# Hydrophone.net
KiCad netlist of a schematic drawn in Altium Designer
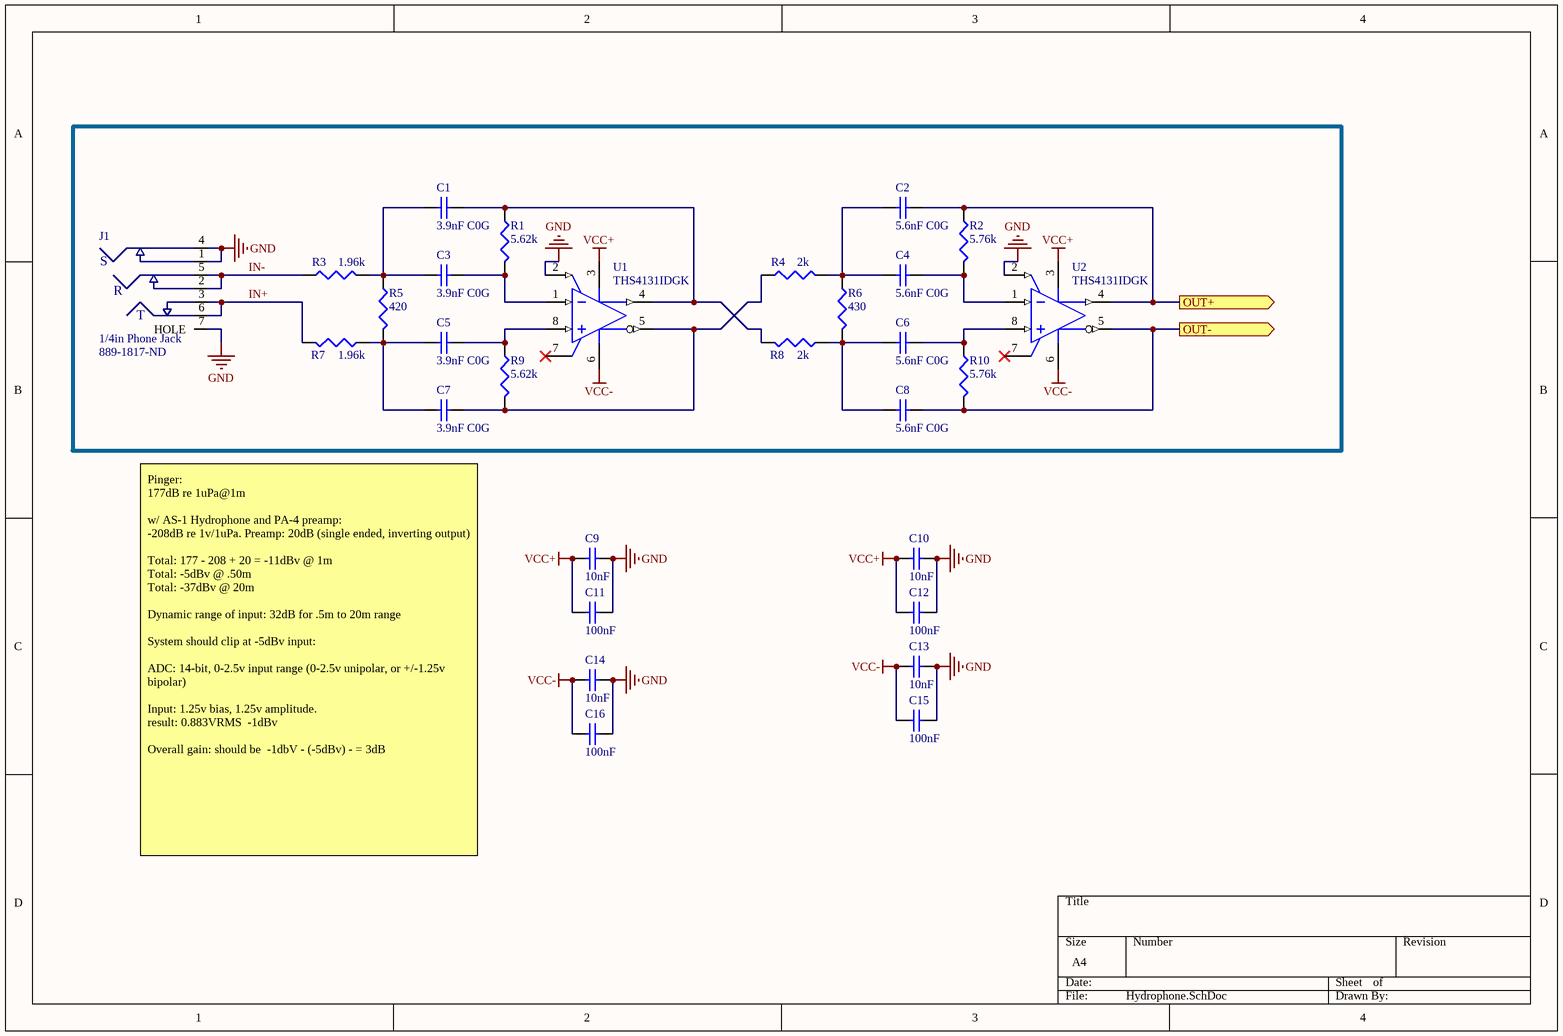
[diagram p0: Hydrophone.SchDoc]

(export (version "E")
  (design (tool "Eeschema 10.0.6"))
  (components
    (comp (ref "C1")
      (value "3.9nF C0G")
      (footprint "CAPC0603(1608)100_M")
      (description "CAP 3.9nF 50V ±20% 0603 (1608 Metric) Thickness 1mm SMD")
      (fields (field (name "TOLERANCE") "Â±20%"))
      (libsource (lib "Altium Content Vault") (part "CAP"))
    )
    (comp (ref "C2")
      (value "5.6nF C0G")
      (footprint "CAPC0603(1608)100_M")
      (description "CAP 5.6nF 50V ±10% 0603 (1608 Metric) Thickness 1mm SMD")
      (fields (field (name "TOLERANCE") "Â±10%"))
      (libsource (lib "Altium Content Vault") (part "CAP"))
    )
    (comp (ref "C3")
      (value "3.9nF C0G")
      (footprint "CAPC0603(1608)100_M")
      (description "CAP 3.9nF 50V ±20% 0603 (1608 Metric) Thickness 1mm SMD")
      (fields (field (name "TOLERANCE") "Â±20%"))
      (libsource (lib "Altium Content Vault") (part "CAP"))
    )
    (comp (ref "C4")
      (value "5.6nF C0G")
      (footprint "CAPC0603(1608)100_M")
      (description "CAP 5.6nF 50V ±10% 0603 (1608 Metric) Thickness 1mm SMD")
      (fields (field (name "TOLERANCE") "Â±10%"))
      (libsource (lib "Altium Content Vault") (part "CAP"))
    )
    (comp (ref "C5")
      (value "3.9nF C0G")
      (footprint "CAPC0603(1608)100_M")
      (description "CAP 3.9nF 50V ±20% 0603 (1608 Metric) Thickness 1mm SMD")
      (fields (field (name "TOLERANCE") "Â±20%"))
      (libsource (lib "Altium Content Vault") (part "CAP"))
    )
    (comp (ref "C6")
      (value "5.6nF C0G")
      (footprint "CAPC0603(1608)100_M")
      (description "CAP 5.6nF 50V ±10% 0603 (1608 Metric) Thickness 1mm SMD")
      (fields (field (name "TOLERANCE") "Â±10%"))
      (libsource (lib "Altium Content Vault") (part "CAP"))
    )
    (comp (ref "C7")
      (value "3.9nF C0G")
      (footprint "CAPC0603(1608)100_M")
      (description "CAP 3.9nF 50V ±20% 0603 (1608 Metric) Thickness 1mm SMD")
      (fields (field (name "TOLERANCE") "Â±20%"))
      (libsource (lib "Altium Content Vault") (part "CAP"))
    )
    (comp (ref "C8")
      (value "5.6nF C0G")
      (footprint "CAPC0603(1608)100_M")
      (description "CAP 5.6nF 50V ±10% 0603 (1608 Metric) Thickness 1mm SMD")
      (fields (field (name "TOLERANCE") "Â±10%"))
      (libsource (lib "Altium Content Vault") (part "CAP"))
    )
    (comp (ref "C9")
      (value "10nF")
      (footprint "CAPC0603(1608)100_M")
      (description "CAP 10nF 50V ±10% 0603 (1608 Metric) Thickness 1mm SMD")
      (fields (field (name "TOLERANCE") "Â±10%"))
      (libsource (lib "Altium Content Vault") (part "CAP"))
    )
    (comp (ref "C10")
      (value "10nF")
      (footprint "CAPC0603(1608)100_M")
      (description "CAP 10nF 50V ±10% 0603 (1608 Metric) Thickness 1mm SMD")
      (fields (field (name "TOLERANCE") "Â±10%"))
      (libsource (lib "Altium Content Vault") (part "CAP"))
    )
    (comp (ref "C11")
      (value "100nF")
      (footprint "CAPC0603(1608)100_M")
      (description "CAP 100nF 50V ±20% 0603 (1608 Metric) Thickness 1mm SMD")
      (fields (field (name "TOLERANCE") "Â±20%"))
      (libsource (lib "Altium Content Vault") (part "CAP"))
    )
    (comp (ref "C12")
      (value "100nF")
      (footprint "CAPC0603(1608)100_M")
      (description "CAP 100nF 50V ±20% 0603 (1608 Metric) Thickness 1mm SMD")
      (fields (field (name "TOLERANCE") "Â±20%"))
      (libsource (lib "Altium Content Vault") (part "CAP"))
    )
    (comp (ref "C13")
      (value "10nF")
      (footprint "CAPC0603(1608)100_M")
      (description "CAP 10nF 50V ±10% 0603 (1608 Metric) Thickness 1mm SMD")
      (fields (field (name "TOLERANCE") "Â±10%"))
      (libsource (lib "Altium Content Vault") (part "CAP"))
    )
    (comp (ref "C14")
      (value "10nF")
      (footprint "CAPC0603(1608)100_M")
      (description "CAP 10nF 50V ±10% 0603 (1608 Metric) Thickness 1mm SMD")
      (fields (field (name "TOLERANCE") "Â±10%"))
      (libsource (lib "Altium Content Vault") (part "CAP"))
    )
    (comp (ref "C15")
      (value "100nF")
      (footprint "CAPC0603(1608)100_M")
      (description "CAP 100nF 50V ±20% 0603 (1608 Metric) Thickness 1mm SMD")
      (fields (field (name "TOLERANCE") "Â±20%"))
      (libsource (lib "Altium Content Vault") (part "CAP"))
    )
    (comp (ref "C16")
      (value "100nF")
      (footprint "CAPC0603(1608)100_M")
      (description "CAP 100nF 50V ±20% 0603 (1608 Metric) Thickness 1mm SMD")
      (fields (field (name "TOLERANCE") "Â±20%"))
      (libsource (lib "Altium Content Vault") (part "CAP"))
    )
    (comp (ref "J1")
      (value "1/4in Phone Jack")
      (footprint "ACJS-MHDR")
      (fields (field (name "SUPPLIER PART NUMBER 1") "889-1817-ND"))
      (libsource (lib "Tauv-Lib") (part "ACJS-MHDR"))
    )
    (comp (ref "R1")
      (value "5.62k")
      (footprint "J1-0603")
      (description "Resistor")
      (fields (field (name "Comment") "Res3") (field (name "PUBLISHER") "Altium Limited"))
      (libsource (lib "Miscellaneous Devices") (part "Res3"))
    )
    (comp (ref "R2")
      (value "5.76k")
      (footprint "J1-0603")
      (description "Resistor")
      (fields (field (name "Comment") "Res3") (field (name "PUBLISHER") "Altium Limited"))
      (libsource (lib "Miscellaneous Devices") (part "Res3"))
    )
    (comp (ref "R3")
      (value "1.96k")
      (footprint "J1-0603")
      (description "Resistor")
      (fields (field (name "Comment") "Res3") (field (name "PUBLISHER") "Altium Limited"))
      (libsource (lib "Miscellaneous Devices") (part "Res3"))
    )
    (comp (ref "R4")
      (value "2k")
      (footprint "J1-0603")
      (description "Resistor")
      (fields (field (name "Comment") "Res3") (field (name "PUBLISHER") "Altium Limited"))
      (libsource (lib "Miscellaneous Devices") (part "Res3"))
    )
    (comp (ref "R5")
      (value "420")
      (footprint "J1-0603")
      (description "Resistor")
      (fields (field (name "Comment") "Res3") (field (name "PUBLISHER") "Altium Limited"))
      (libsource (lib "Miscellaneous Devices") (part "Res3"))
    )
    (comp (ref "R6")
      (value "430")
      (footprint "J1-0603")
      (description "Resistor")
      (fields (field (name "Comment") "Res3") (field (name "PUBLISHER") "Altium Limited"))
      (libsource (lib "Miscellaneous Devices") (part "Res3"))
    )
    (comp (ref "R7")
      (value "1.96k")
      (footprint "J1-0603")
      (description "Resistor")
      (fields (field (name "Comment") "Res3") (field (name "PUBLISHER") "Altium Limited"))
      (libsource (lib "Miscellaneous Devices") (part "Res3"))
    )
    (comp (ref "R8")
      (value "2k")
      (footprint "J1-0603")
      (description "Resistor")
      (fields (field (name "Comment") "Res3") (field (name "PUBLISHER") "Altium Limited"))
      (libsource (lib "Miscellaneous Devices") (part "Res3"))
    )
    (comp (ref "R9")
      (value "5.62k")
      (footprint "J1-0603")
      (description "Resistor")
      (fields (field (name "Comment") "Res3") (field (name "PUBLISHER") "Altium Limited"))
      (libsource (lib "Miscellaneous Devices") (part "Res3"))
    )
    (comp (ref "R10")
      (value "5.76k")
      (footprint "J1-0603")
      (description "Resistor")
      (fields (field (name "Comment") "Res3") (field (name "PUBLISHER") "Altium Limited"))
      (libsource (lib "Miscellaneous Devices") (part "Res3"))
    )
    (comp (ref "U1")
      (value "THS4131IDGK")
      (footprint "DGK0008A_N")
      (fields (field (name "MANUFACTURER") "Texas Instruments"))
      (libsource (lib "Altium Content Vault") (part "TI-THS41X1-8"))
    )
    (comp (ref "U2")
      (value "THS4131IDGK")
      (footprint "DGK0008A_N")
      (fields (field (name "MANUFACTURER") "Texas Instruments"))
      (libsource (lib "Altium Content Vault") (part "TI-THS41X1-8"))
    )
  )
  (nets
    (net (code "1") (name "/IN+") (class "Default")
      (node (ref "J1") (pin "3") (pinfunction "3_3") (pintype "passive"))
      (node (ref "J1") (pin "6") (pinfunction "6_6") (pintype "passive"))
      (node (ref "R7") (pin "2") (pinfunction "2_2") (pintype "passive"))
    )
    (net (code "2") (name "/IN-") (class "Default")
      (node (ref "J1") (pin "2") (pinfunction "2_2") (pintype "passive"))
      (node (ref "J1") (pin "5") (pinfunction "5_5") (pintype "passive"))
      (node (ref "R3") (pin "1") (pinfunction "1_1") (pintype "passive"))
    )
    (net (code "3") (name "/OUT+") (class "Default")
      (node (ref "C2") (pin "2") (pinfunction "2_2") (pintype "passive"))
      (node (ref "R2") (pin "1") (pinfunction "1_1") (pintype "passive"))
      (node (ref "U2") (pin "4") (pinfunction "VOUT+_4") (pintype "output"))
    )
    (net (code "4") (name "/OUT-") (class "Default")
      (node (ref "C8") (pin "2") (pinfunction "2_2") (pintype "passive"))
      (node (ref "R10") (pin "2") (pinfunction "2_2") (pintype "passive"))
      (node (ref "U2") (pin "5") (pinfunction "VOUT-_5") (pintype "output"))
    )
    (net (code "5") (name "GND") (class "Default")
      (node (ref "C10") (pin "2") (pinfunction "2_2") (pintype "passive"))
      (node (ref "C11") (pin "2") (pinfunction "2_2") (pintype "passive"))
      (node (ref "C12") (pin "2") (pinfunction "2_2") (pintype "passive"))
      (node (ref "C13") (pin "2") (pinfunction "2_2") (pintype "passive"))
      (node (ref "C14") (pin "2") (pinfunction "2_2") (pintype "passive"))
      (node (ref "C15") (pin "2") (pinfunction "2_2") (pintype "passive"))
      (node (ref "C16") (pin "2") (pinfunction "2_2") (pintype "passive"))
      (node (ref "C9") (pin "2") (pinfunction "2_2") (pintype "passive"))
      (node (ref "J1") (pin "1") (pinfunction "1_1") (pintype "passive"))
      (node (ref "J1") (pin "4") (pinfunction "4_4") (pintype "passive"))
      (node (ref "J1") (pin "7") (pinfunction "HOLE_7") (pintype "passive"))
      (node (ref "U1") (pin "2") (pinfunction "VOCM_2") (pintype "input"))
      (node (ref "U2") (pin "2") (pinfunction "VOCM_2") (pintype "input"))
    )
    (net (code "6") (name "Net-(C1-Pad1)") (class "Default")
      (node (ref "C1") (pin "1") (pinfunction "1_1") (pintype "passive"))
      (node (ref "C3") (pin "1") (pinfunction "1_1") (pintype "passive"))
      (node (ref "R3") (pin "2") (pinfunction "2_2") (pintype "passive"))
      (node (ref "R5") (pin "1") (pinfunction "1_1") (pintype "passive"))
    )
    (net (code "7") (name "Net-(C2-Pad1)") (class "Default")
      (node (ref "C2") (pin "1") (pinfunction "1_1") (pintype "passive"))
      (node (ref "C4") (pin "1") (pinfunction "1_1") (pintype "passive"))
      (node (ref "R4") (pin "2") (pinfunction "2_2") (pintype "passive"))
      (node (ref "R6") (pin "1") (pinfunction "1_1") (pintype "passive"))
    )
    (net (code "8") (name "Net-(C5-Pad1)") (class "Default")
      (node (ref "C5") (pin "1") (pinfunction "1_1") (pintype "passive"))
      (node (ref "C7") (pin "1") (pinfunction "1_1") (pintype "passive"))
      (node (ref "R5") (pin "2") (pinfunction "2_2") (pintype "passive"))
      (node (ref "R7") (pin "1") (pinfunction "1_1") (pintype "passive"))
    )
    (net (code "9") (name "Net-(C6-Pad1)") (class "Default")
      (node (ref "C6") (pin "1") (pinfunction "1_1") (pintype "passive"))
      (node (ref "C8") (pin "1") (pinfunction "1_1") (pintype "passive"))
      (node (ref "R6") (pin "2") (pinfunction "2_2") (pintype "passive"))
      (node (ref "R8") (pin "1") (pinfunction "1_1") (pintype "passive"))
    )
    (net (code "10") (name "Net-(U1-VIN+)") (class "Default")
      (node (ref "C5") (pin "2") (pinfunction "2_2") (pintype "passive"))
      (node (ref "R9") (pin "1") (pinfunction "1_1") (pintype "passive"))
      (node (ref "U1") (pin "8") (pinfunction "VIN+_8") (pintype "input"))
    )
    (net (code "11") (name "Net-(U1-VIN-)") (class "Default")
      (node (ref "C3") (pin "2") (pinfunction "2_2") (pintype "passive"))
      (node (ref "R1") (pin "2") (pinfunction "2_2") (pintype "passive"))
      (node (ref "U1") (pin "1") (pinfunction "VIN-_1") (pintype "input"))
    )
    (net (code "12") (name "Net-(U1-VOUT+)") (class "Default")
      (node (ref "C1") (pin "2") (pinfunction "2_2") (pintype "passive"))
      (node (ref "R1") (pin "1") (pinfunction "1_1") (pintype "passive"))
      (node (ref "R8") (pin "2") (pinfunction "2_2") (pintype "passive"))
      (node (ref "U1") (pin "4") (pinfunction "VOUT+_4") (pintype "output"))
    )
    (net (code "13") (name "Net-(U1-VOUT-)") (class "Default")
      (node (ref "C7") (pin "2") (pinfunction "2_2") (pintype "passive"))
      (node (ref "R4") (pin "1") (pinfunction "1_1") (pintype "passive"))
      (node (ref "R9") (pin "2") (pinfunction "2_2") (pintype "passive"))
      (node (ref "U1") (pin "5") (pinfunction "VOUT-_5") (pintype "output"))
    )
    (net (code "14") (name "Net-(U2-VIN+)") (class "Default")
      (node (ref "C6") (pin "2") (pinfunction "2_2") (pintype "passive"))
      (node (ref "R10") (pin "1") (pinfunction "1_1") (pintype "passive"))
      (node (ref "U2") (pin "8") (pinfunction "VIN+_8") (pintype "input"))
    )
    (net (code "15") (name "Net-(U2-VIN-)") (class "Default")
      (node (ref "C4") (pin "2") (pinfunction "2_2") (pintype "passive"))
      (node (ref "R2") (pin "2") (pinfunction "2_2") (pintype "passive"))
      (node (ref "U2") (pin "1") (pinfunction "VIN-_1") (pintype "input"))
    )
    (net (code "16") (name "VCC+") (class "Default")
      (node (ref "C10") (pin "1") (pinfunction "1_1") (pintype "passive"))
      (node (ref "C11") (pin "1") (pinfunction "1_1") (pintype "passive"))
      (node (ref "C12") (pin "1") (pinfunction "1_1") (pintype "passive"))
      (node (ref "C9") (pin "1") (pinfunction "1_1") (pintype "passive"))
      (node (ref "U1") (pin "3") (pinfunction "VCC+_3") (pintype "power_in"))
      (node (ref "U2") (pin "3") (pinfunction "VCC+_3") (pintype "power_in"))
    )
    (net (code "17") (name "VCC-") (class "Default")
      (node (ref "C13") (pin "1") (pinfunction "1_1") (pintype "passive"))
      (node (ref "C14") (pin "1") (pinfunction "1_1") (pintype "passive"))
      (node (ref "C15") (pin "1") (pinfunction "1_1") (pintype "passive"))
      (node (ref "C16") (pin "1") (pinfunction "1_1") (pintype "passive"))
      (node (ref "U1") (pin "6") (pinfunction "VCC-_6") (pintype "power_in"))
      (node (ref "U2") (pin "6") (pinfunction "VCC-_6") (pintype "power_in"))
    )
    (net (code "18") (name "unconnected-(U1-NC-Pad7)") (class "Default")
      (node (ref "U1") (pin "7") (pinfunction "NC_7") (pintype "passive+no_connect"))
    )
    (net (code "19") (name "unconnected-(U2-NC-Pad7)") (class "Default")
      (node (ref "U2") (pin "7") (pinfunction "NC_7") (pintype "passive+no_connect"))
    )
  )
)
